# cavedweller.net
KiCad netlist of a schematic drawn in EAGLE
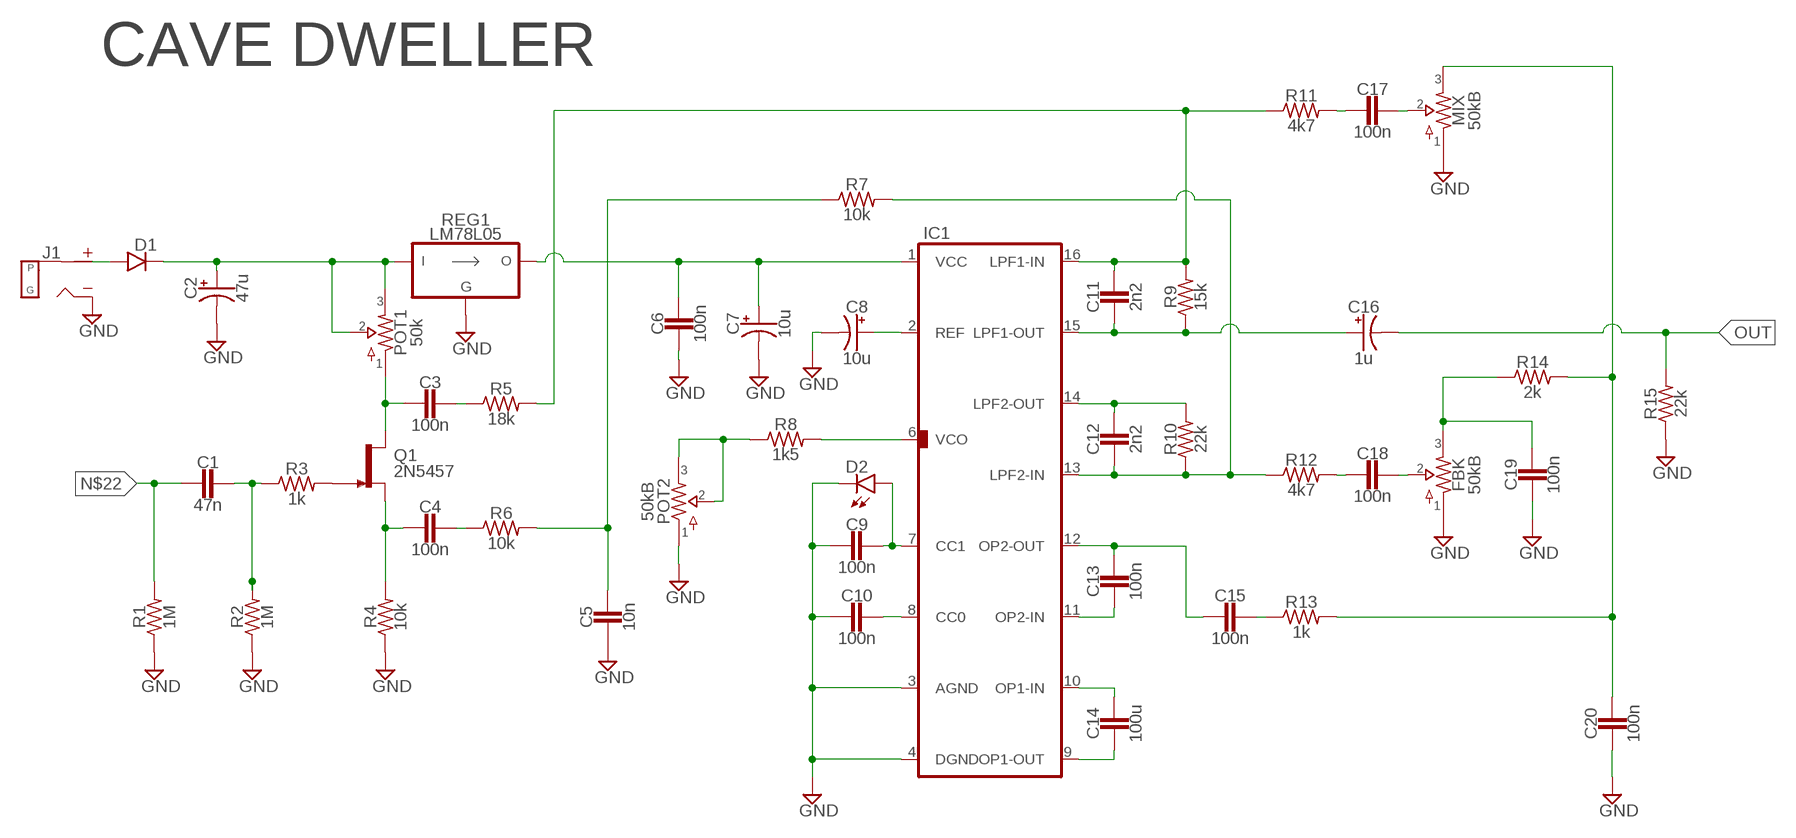
[diagram p0: schematic, sheet 1]

(export (version "E")
  (design (tool "Eeschema 10.0.6"))
  (components
    (comp (ref "C1")
      (value "47n")
      (footprint "eagle-import:050X030_025_2")
      (libsource (lib "eagle-import") (part "CER/FILM2"))
    )
    (comp (ref "C2")
      (value "47u")
      (footprint "eagle-import:050_020_1")
      (libsource (lib "eagle-import") (part "0501"))
    )
    (comp (ref "C3")
      (value "100n")
      (footprint "eagle-import:050X030_025_2")
      (libsource (lib "eagle-import") (part "CER/FILM2"))
    )
    (comp (ref "C4")
      (value "100n")
      (footprint "eagle-import:050X030_025_2")
      (libsource (lib "eagle-import") (part "CER/FILM2"))
    )
    (comp (ref "C5")
      (value "10n")
      (footprint "eagle-import:050X030_025_2")
      (libsource (lib "eagle-import") (part "CER/FILM2"))
    )
    (comp (ref "C6")
      (value "100n")
      (footprint "eagle-import:050X030_025_2")
      (libsource (lib "eagle-import") (part "CER/FILM2"))
    )
    (comp (ref "C7")
      (value "10u")
      (footprint "eagle-import:050_020_1")
      (libsource (lib "eagle-import") (part "0501"))
    )
    (comp (ref "C8")
      (value "10u")
      (footprint "eagle-import:050_020_1")
      (libsource (lib "eagle-import") (part "0501"))
    )
    (comp (ref "C9")
      (value "100n")
      (footprint "eagle-import:050X030_025_2")
      (libsource (lib "eagle-import") (part "CER/FILM2"))
    )
    (comp (ref "C10")
      (value "100n")
      (footprint "eagle-import:050X030_025_2")
      (libsource (lib "eagle-import") (part "CER/FILM2"))
    )
    (comp (ref "C11")
      (value "2n2")
      (footprint "eagle-import:050X030_025_2")
      (libsource (lib "eagle-import") (part "CER/FILM2"))
    )
    (comp (ref "C12")
      (value "2n2")
      (footprint "eagle-import:050X030_025_2")
      (libsource (lib "eagle-import") (part "CER/FILM2"))
    )
    (comp (ref "C13")
      (value "100n")
      (footprint "eagle-import:050X030_025_2")
      (libsource (lib "eagle-import") (part "CER/FILM2"))
    )
    (comp (ref "C14")
      (value "100u")
      (footprint "eagle-import:050X030_025_2")
      (libsource (lib "eagle-import") (part "CER/FILM2"))
    )
    (comp (ref "C15")
      (value "100n")
      (footprint "eagle-import:050X030_025_2")
      (libsource (lib "eagle-import") (part "CER/FILM2"))
    )
    (comp (ref "C16")
      (value "1u")
      (footprint "eagle-import:050_020_1")
      (libsource (lib "eagle-import") (part "0501"))
    )
    (comp (ref "C17")
      (value "100n")
      (footprint "eagle-import:050X030_025_2")
      (libsource (lib "eagle-import") (part "CER/FILM2"))
    )
    (comp (ref "C18")
      (value "100n")
      (footprint "eagle-import:050X030_025_2")
      (libsource (lib "eagle-import") (part "CER/FILM2"))
    )
    (comp (ref "C19")
      (value "100n")
      (footprint "eagle-import:050X030_025_2")
      (libsource (lib "eagle-import") (part "CER/FILM2"))
    )
    (comp (ref "C20")
      (value "100n")
      (footprint "eagle-import:050X030_025_2")
      (libsource (lib "eagle-import") (part "CER/FILM2"))
    )
    (comp (ref "D1")
      (value "DO41.3")
      (footprint "eagle-import:DO41-3")
      (libsource (lib "eagle-import") (part "DO41.3"))
    )
    (comp (ref "D2")
      (value "LEDB")
      (footprint "eagle-import:3MM_B")
      (libsource (lib "eagle-import") (part "LEDB"))
    )
    (comp (ref "FBK")
      (value "50kB")
      (footprint "eagle-import:PADS_SMALL")
      (libsource (lib "eagle-import") (part "POTSSMALL_PADS"))
    )
    (comp (ref "IC1")
      (value "PT2399TH")
      (footprint "eagle-import:DIL16")
      (libsource (lib "eagle-import") (part "PT2399TH"))
    )
    (comp (ref "J1")
      (value "DC_MONO")
      (footprint "eagle-import:DC")
      (libsource (lib "eagle-import") (part "DC_MONO"))
    )
    (comp (ref "MIX")
      (value "50kB")
      (footprint "eagle-import:PADS_SMALL")
      (libsource (lib "eagle-import") (part "POTSSMALL_PADS"))
    )
    (comp (ref "POT1")
      (value "50k")
      (footprint "eagle-import:2262_TRIM")
      (libsource (lib "eagle-import") (part "POTSTRIM"))
    )
    (comp (ref "POT2")
      (value "50kB")
      (footprint "eagle-import:PADS_SMALL")
      (libsource (lib "eagle-import") (part "POTSSMALL_PADS"))
    )
    (comp (ref "Q1")
      (value "2N5457")
      (footprint "eagle-import:TO92-")
      (libsource (lib "eagle-import") (part "2N5457"))
    )
    (comp (ref "R1")
      (value "1M")
      (footprint "eagle-import:R0207_2V")
      (libsource (lib "eagle-import") (part "R_.2"))
    )
    (comp (ref "R2")
      (value "1M")
      (footprint "eagle-import:R0207_2V")
      (libsource (lib "eagle-import") (part "R_.2"))
    )
    (comp (ref "R3")
      (value "1k")
      (footprint "eagle-import:R0207_2V")
      (libsource (lib "eagle-import") (part "R_.2"))
    )
    (comp (ref "R4")
      (value "10k")
      (footprint "eagle-import:R0207_2V")
      (libsource (lib "eagle-import") (part "R_.2"))
    )
    (comp (ref "R5")
      (value "18k")
      (footprint "eagle-import:R0207_2V")
      (libsource (lib "eagle-import") (part "R_.2"))
    )
    (comp (ref "R6")
      (value "10k")
      (footprint "eagle-import:R0207_2V")
      (libsource (lib "eagle-import") (part "R_.2"))
    )
    (comp (ref "R7")
      (value "10k")
      (footprint "eagle-import:R0207_2V")
      (libsource (lib "eagle-import") (part "R_.2"))
    )
    (comp (ref "R8")
      (value "1k5")
      (footprint "eagle-import:R0207_2V")
      (libsource (lib "eagle-import") (part "R_.2"))
    )
    (comp (ref "R9")
      (value "15k")
      (footprint "eagle-import:R0207_2V")
      (libsource (lib "eagle-import") (part "R_.2"))
    )
    (comp (ref "R10")
      (value "22k")
      (footprint "eagle-import:R0207_2V")
      (libsource (lib "eagle-import") (part "R_.2"))
    )
    (comp (ref "R11")
      (value "4k7")
      (footprint "eagle-import:R0207_2V")
      (libsource (lib "eagle-import") (part "R_.2"))
    )
    (comp (ref "R12")
      (value "4k7")
      (footprint "eagle-import:R0207_2V")
      (libsource (lib "eagle-import") (part "R_.2"))
    )
    (comp (ref "R13")
      (value "1k")
      (footprint "eagle-import:R0207_2V")
      (libsource (lib "eagle-import") (part "R_.2"))
    )
    (comp (ref "R14")
      (value "2k")
      (footprint "eagle-import:R0207_2V")
      (libsource (lib "eagle-import") (part "R_.2"))
    )
    (comp (ref "R15")
      (value "22k")
      (footprint "eagle-import:R0207_2V")
      (libsource (lib "eagle-import") (part "R_.2"))
    )
    (comp (ref "REG1")
      (value "LM78L05")
      (footprint "eagle-import:TO92-")
      (libsource (lib "eagle-import") (part "LM78L05"))
    )
  )
  (nets
    (net (code "1") (name "GND") (class "Default")
      (node (ref "C10") (pin "2") (pinfunction "2_2") (pintype "passive"))
      (node (ref "C19") (pin "2") (pinfunction "2_2") (pintype "passive"))
      (node (ref "C2") (pin "-") (pinfunction "-_-") (pintype "passive"))
      (node (ref "C20") (pin "2") (pinfunction "2_2") (pintype "passive"))
      (node (ref "C5") (pin "2") (pinfunction "2_2") (pintype "passive"))
      (node (ref "C6") (pin "2") (pinfunction "2_2") (pintype "passive"))
      (node (ref "C7") (pin "-") (pinfunction "-_-") (pintype "passive"))
      (node (ref "C8") (pin "-") (pinfunction "-_-") (pintype "passive"))
      (node (ref "C9") (pin "2") (pinfunction "2_2") (pintype "passive"))
      (node (ref "D2") (pin "K") (pinfunction "C_K") (pintype "passive"))
      (node (ref "FBK") (pin "1") (pinfunction "1_1") (pintype "passive"))
      (node (ref "IC1") (pin "3") (pinfunction "AGND_3") (pintype "power_in"))
      (node (ref "IC1") (pin "4") (pinfunction "DGND_4") (pintype "power_in"))
      (node (ref "J1") (pin "S") (pinfunction "SLEEVE_S") (pintype "passive"))
      (node (ref "MIX") (pin "1") (pinfunction "1_1") (pintype "passive"))
      (node (ref "POT2") (pin "1") (pinfunction "1_1") (pintype "passive"))
      (node (ref "R1") (pin "1") (pinfunction "1_1") (pintype "passive"))
      (node (ref "R15") (pin "1") (pinfunction "1_1") (pintype "passive"))
      (node (ref "R2") (pin "1") (pinfunction "1_1") (pintype "passive"))
      (node (ref "R4") (pin "1") (pinfunction "1_1") (pintype "passive"))
      (node (ref "REG1") (pin "2") (pinfunction "GND_2") (pintype "passive"))
    )
    (net (code "2") (name "N$22") (class "Default")
      (node (ref "C1") (pin "2") (pinfunction "2_2") (pintype "passive"))
      (node (ref "R1") (pin "2") (pinfunction "2_2") (pintype "passive"))
    )
    (net (code "3") (name "Net-(C1-Pad1)") (class "Default")
      (node (ref "C1") (pin "1") (pinfunction "1_1") (pintype "passive"))
      (node (ref "R2") (pin "2") (pinfunction "2_2") (pintype "passive"))
      (node (ref "R3") (pin "1") (pinfunction "1_1") (pintype "passive"))
    )
    (net (code "4") (name "Net-(C3-Pad1)") (class "Default")
      (node (ref "C3") (pin "1") (pinfunction "1_1") (pintype "passive"))
      (node (ref "R5") (pin "1") (pinfunction "1_1") (pintype "passive"))
    )
    (net (code "5") (name "Net-(C4-Pad1)") (class "Default")
      (node (ref "C4") (pin "1") (pinfunction "1_1") (pintype "passive"))
      (node (ref "R6") (pin "1") (pinfunction "1_1") (pintype "passive"))
    )
    (net (code "6") (name "Net-(C5-Pad1)") (class "Default")
      (node (ref "C5") (pin "1") (pinfunction "1_1") (pintype "passive"))
      (node (ref "R6") (pin "2") (pinfunction "2_2") (pintype "passive"))
      (node (ref "R7") (pin "1") (pinfunction "1_1") (pintype "passive"))
    )
    (net (code "7") (name "Net-(C15-Pad1)") (class "Default")
      (node (ref "C15") (pin "1") (pinfunction "1_1") (pintype "passive"))
      (node (ref "R13") (pin "1") (pinfunction "1_1") (pintype "passive"))
    )
    (net (code "8") (name "Net-(C17-Pad1)") (class "Default")
      (node (ref "C17") (pin "1") (pinfunction "1_1") (pintype "passive"))
      (node (ref "MIX") (pin "2") (pinfunction "2_2") (pintype "passive"))
    )
    (net (code "9") (name "Net-(C17-Pad2)") (class "Default")
      (node (ref "C17") (pin "2") (pinfunction "2_2") (pintype "passive"))
      (node (ref "R11") (pin "2") (pinfunction "2_2") (pintype "passive"))
    )
    (net (code "10") (name "Net-(C18-Pad1)") (class "Default")
      (node (ref "C18") (pin "1") (pinfunction "1_1") (pintype "passive"))
      (node (ref "FBK") (pin "2") (pinfunction "2_2") (pintype "passive"))
    )
    (net (code "11") (name "Net-(C18-Pad2)") (class "Default")
      (node (ref "C18") (pin "2") (pinfunction "2_2") (pintype "passive"))
      (node (ref "R12") (pin "2") (pinfunction "2_2") (pintype "passive"))
    )
    (net (code "12") (name "Net-(C19-Pad1)") (class "Default")
      (node (ref "C19") (pin "1") (pinfunction "1_1") (pintype "passive"))
      (node (ref "FBK") (pin "3") (pinfunction "3_3") (pintype "passive"))
      (node (ref "R14") (pin "1") (pinfunction "1_1") (pintype "passive"))
    )
    (net (code "13") (name "Net-(C20-Pad1)") (class "Default")
      (node (ref "C20") (pin "1") (pinfunction "1_1") (pintype "passive"))
      (node (ref "MIX") (pin "3") (pinfunction "3_3") (pintype "passive"))
      (node (ref "R13") (pin "2") (pinfunction "2_2") (pintype "passive"))
      (node (ref "R14") (pin "2") (pinfunction "2_2") (pintype "passive"))
    )
    (net (code "14") (name "Net-(IC1-CC0)") (class "Default")
      (node (ref "C10") (pin "1") (pinfunction "1_1") (pintype "passive"))
      (node (ref "IC1") (pin "8") (pinfunction "CC0_8") (pintype "input"))
    )
    (net (code "15") (name "Net-(IC1-CC1)") (class "Default")
      (node (ref "C9") (pin "1") (pinfunction "1_1") (pintype "passive"))
      (node (ref "D2") (pin "A") (pinfunction "A_A") (pintype "passive"))
      (node (ref "IC1") (pin "7") (pinfunction "CC1_7") (pintype "input"))
    )
    (net (code "16") (name "Net-(IC1-LPF1-IN)") (class "Default")
      (node (ref "C11") (pin "1") (pinfunction "1_1") (pintype "passive"))
      (node (ref "IC1") (pin "16") (pinfunction "LPF1-IN_16") (pintype "input"))
      (node (ref "R11") (pin "1") (pinfunction "1_1") (pintype "passive"))
      (node (ref "R5") (pin "2") (pinfunction "2_2") (pintype "passive"))
      (node (ref "R9") (pin "2") (pinfunction "2_2") (pintype "passive"))
    )
    (net (code "17") (name "Net-(IC1-LPF1-OUT)") (class "Default")
      (node (ref "C11") (pin "2") (pinfunction "2_2") (pintype "passive"))
      (node (ref "C16") (pin "+") (pinfunction "+_+") (pintype "passive"))
      (node (ref "IC1") (pin "15") (pinfunction "LPF1-OUT_15") (pintype "output"))
      (node (ref "R9") (pin "1") (pinfunction "1_1") (pintype "passive"))
    )
    (net (code "18") (name "Net-(IC1-LPF2-IN)") (class "Default")
      (node (ref "C12") (pin "2") (pinfunction "2_2") (pintype "passive"))
      (node (ref "IC1") (pin "13") (pinfunction "LPF2-IN_13") (pintype "input"))
      (node (ref "R10") (pin "1") (pinfunction "1_1") (pintype "passive"))
      (node (ref "R12") (pin "1") (pinfunction "1_1") (pintype "passive"))
      (node (ref "R7") (pin "2") (pinfunction "2_2") (pintype "passive"))
    )
    (net (code "19") (name "Net-(IC1-LPF2-OUT)") (class "Default")
      (node (ref "C12") (pin "1") (pinfunction "1_1") (pintype "passive"))
      (node (ref "IC1") (pin "14") (pinfunction "LPF2-OUT_14") (pintype "output"))
      (node (ref "R10") (pin "2") (pinfunction "2_2") (pintype "passive"))
    )
    (net (code "20") (name "Net-(IC1-OP1-IN)") (class "Default")
      (node (ref "C14") (pin "1") (pinfunction "1_1") (pintype "passive"))
      (node (ref "IC1") (pin "10") (pinfunction "OP1-IN_10") (pintype "input"))
    )
    (net (code "21") (name "Net-(IC1-OP1-OUT)") (class "Default")
      (node (ref "C14") (pin "2") (pinfunction "2_2") (pintype "passive"))
      (node (ref "IC1") (pin "9") (pinfunction "OP1-OUT_9") (pintype "output"))
    )
    (net (code "22") (name "Net-(IC1-OP2-IN)") (class "Default")
      (node (ref "C13") (pin "2") (pinfunction "2_2") (pintype "passive"))
      (node (ref "IC1") (pin "11") (pinfunction "OP2-IN_11") (pintype "input"))
    )
    (net (code "23") (name "Net-(IC1-OP2-OUT)") (class "Default")
      (node (ref "C13") (pin "1") (pinfunction "1_1") (pintype "passive"))
      (node (ref "C15") (pin "2") (pinfunction "2_2") (pintype "passive"))
      (node (ref "IC1") (pin "12") (pinfunction "OP2-OUT_12") (pintype "output"))
    )
    (net (code "24") (name "Net-(IC1-REF)") (class "Default")
      (node (ref "C8") (pin "+") (pinfunction "+_+") (pintype "passive"))
      (node (ref "IC1") (pin "2") (pinfunction "REF_2") (pintype "input"))
    )
    (net (code "25") (name "Net-(IC1-VCC)") (class "Default")
      (node (ref "C6") (pin "1") (pinfunction "1_1") (pintype "passive"))
      (node (ref "C7") (pin "+") (pinfunction "+_+") (pintype "passive"))
      (node (ref "IC1") (pin "1") (pinfunction "VCC_1") (pintype "power_in"))
      (node (ref "REG1") (pin "3") (pinfunction "VO_3") (pintype "passive"))
    )
    (net (code "26") (name "Net-(IC1-VCO)") (class "Default")
      (node (ref "IC1") (pin "6") (pinfunction "VCO_6") (pintype "input"))
      (node (ref "R8") (pin "2") (pinfunction "2_2") (pintype "passive"))
    )
    (net (code "27") (name "Net-(J1-TIP)") (class "Default")
      (node (ref "D1") (pin "A") (pinfunction "A_A") (pintype "passive"))
      (node (ref "J1") (pin "T") (pinfunction "TIP_T") (pintype "passive"))
    )
    (net (code "28") (name "Net-(POT2-Pad2)") (class "Default")
      (node (ref "POT2") (pin "2") (pinfunction "2_2") (pintype "passive"))
      (node (ref "POT2") (pin "3") (pinfunction "3_3") (pintype "passive"))
      (node (ref "R8") (pin "1") (pinfunction "1_1") (pintype "passive"))
    )
    (net (code "29") (name "Net-(Q1-D)") (class "Default")
      (node (ref "C3") (pin "2") (pinfunction "2_2") (pintype "passive"))
      (node (ref "POT1") (pin "1") (pinfunction "1_1") (pintype "passive"))
      (node (ref "Q1") (pin "3") (pinfunction "D_3") (pintype "passive"))
    )
    (net (code "30") (name "Net-(Q1-G)") (class "Default")
      (node (ref "Q1") (pin "1") (pinfunction "G_1") (pintype "passive"))
      (node (ref "R3") (pin "2") (pinfunction "2_2") (pintype "passive"))
    )
    (net (code "31") (name "Net-(Q1-S)") (class "Default")
      (node (ref "C4") (pin "2") (pinfunction "2_2") (pintype "passive"))
      (node (ref "Q1") (pin "2") (pinfunction "S_2") (pintype "passive"))
      (node (ref "R4") (pin "2") (pinfunction "2_2") (pintype "passive"))
    )
    (net (code "32") (name "Net-(REG1-VI)") (class "Default")
      (node (ref "C2") (pin "+") (pinfunction "+_+") (pintype "passive"))
      (node (ref "D1") (pin "C") (pinfunction "C_C") (pintype "passive"))
      (node (ref "POT1") (pin "2") (pinfunction "2_2") (pintype "passive"))
      (node (ref "POT1") (pin "3") (pinfunction "3_3") (pintype "passive"))
      (node (ref "REG1") (pin "1") (pinfunction "VI_1") (pintype "input"))
    )
    (net (code "33") (name "OUT") (class "Default")
      (node (ref "C16") (pin "-") (pinfunction "-_-") (pintype "passive"))
      (node (ref "R15") (pin "2") (pinfunction "2_2") (pintype "passive"))
    )
  )
)
